# slave_node_v0_1.net
KiCad netlist of a schematic drawn in EAGLE
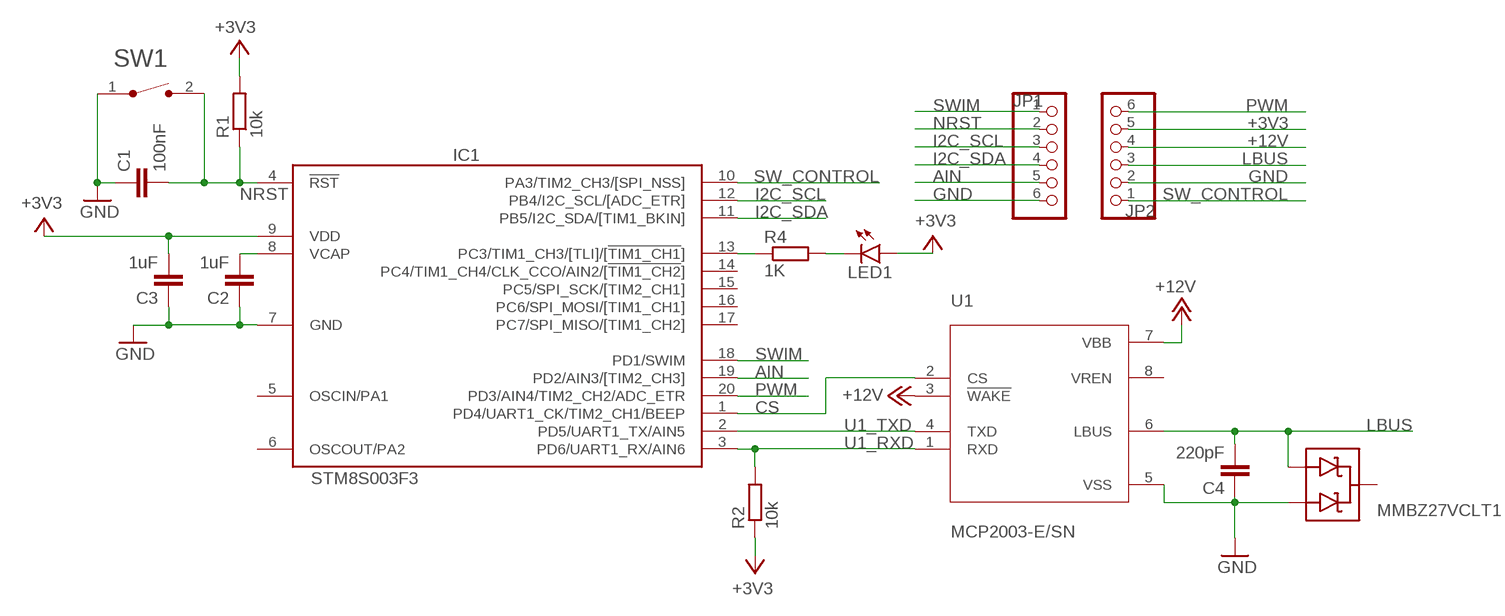
[diagram p0: schematic, sheet 1]
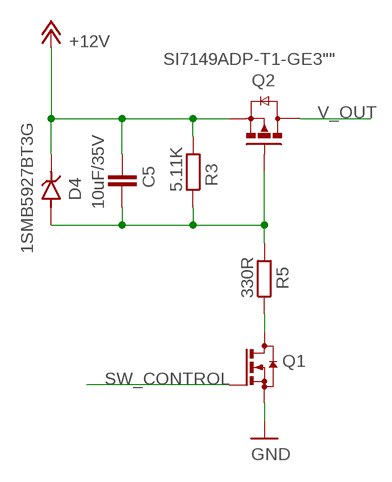
[diagram p1: schematic, sheet 2]
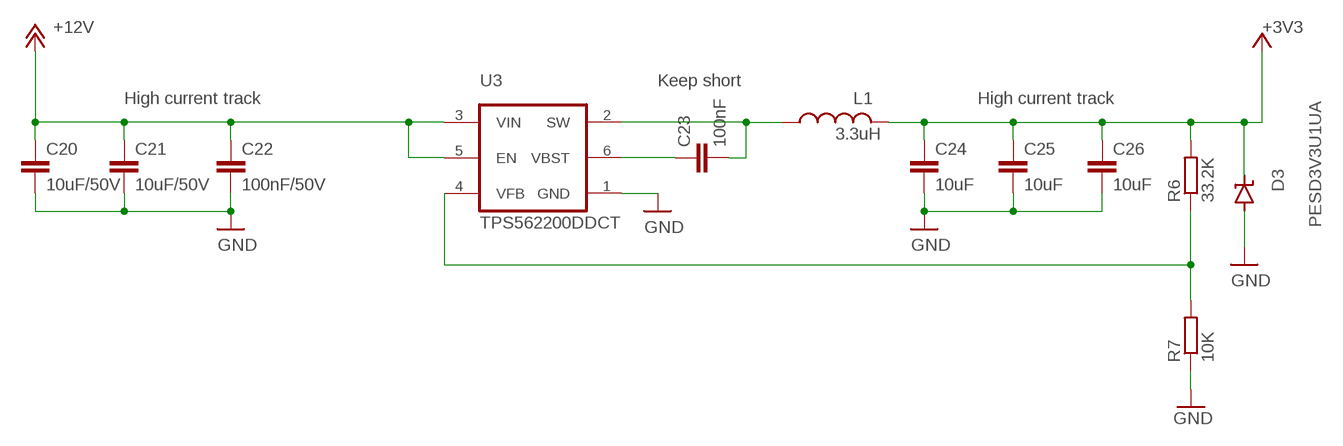
[diagram p2: schematic, sheet 3]

(export (version "E")
  (design (tool "Eeschema 10.0.6"))
  (components
    (comp (ref "C20")
      (value "10uF/50V")
      (footprint "eagle-import:C0603")
      (libsource (lib "eagle-import") (part "C-EUC0603"))
    )
    (comp (ref "C21")
      (value "10uF/50V")
      (footprint "eagle-import:C0603")
      (libsource (lib "eagle-import") (part "C-EUC0603"))
    )
    (comp (ref "C22")
      (value "100nF/50V")
      (footprint "eagle-import:C0603")
      (libsource (lib "eagle-import") (part "C-EUC0603"))
    )
    (comp (ref "C23")
      (value "100nF")
      (footprint "eagle-import:C0603")
      (libsource (lib "eagle-import") (part "C-EUC0603"))
    )
    (comp (ref "C24")
      (value "10uF")
      (footprint "eagle-import:C0603")
      (libsource (lib "eagle-import") (part "C-EUC0603"))
    )
    (comp (ref "C25")
      (value "10uF")
      (footprint "eagle-import:C0603")
      (libsource (lib "eagle-import") (part "C-EUC0603"))
    )
    (comp (ref "C26")
      (value "10uF")
      (footprint "eagle-import:C0603")
      (libsource (lib "eagle-import") (part "C-EUC0603"))
    )
    (comp (ref "D3")
      (value "PESD3V3U1UA")
      (footprint "eagle-import:SOD323")
      (libsource (lib "eagle-import") (part "PESD3V3U1UA"))
    )
    (comp (ref "L1")
      (value "3.3uH")
      (footprint "eagle-import:INDC2520X120N")
      (fields
        (field (name "DIGI-KEY_PART_NUMBER") "587-4723-1-ND")
        (field (name "MF") "Taiyo Yuden")
        (field (name "MP") "MBMK2520H3R3M")
      )
      (libsource (lib "eagle-import") (part "MBMK2520H3R3M"))
    )
    (comp (ref "R6")
      (value "33.2K")
      (footprint "eagle-import:R0603")
      (libsource (lib "eagle-import") (part "R-EU_R0603"))
    )
    (comp (ref "R7")
      (value "10K")
      (footprint "eagle-import:R0603")
      (libsource (lib "eagle-import") (part "R-EU_R0603"))
    )
    (comp (ref "U3")
      (value "TPS562200DDCT")
      (footprint "eagle-import:SOT95P280X110-6N")
      (fields (field (name "MF") "Texas Instruments"))
      (libsource (lib "eagle-import") (part "TPS562200DDCT"))
    )
    (comp (ref "C1")
      (value "100nF")
      (footprint "eagle-import:C0603")
      (libsource (lib "eagle-import") (part "C-EUC0603"))
    )
    (comp (ref "C2")
      (value "1uF")
      (footprint "eagle-import:C0603")
      (libsource (lib "eagle-import") (part "C-EUC0603"))
    )
    (comp (ref "C3")
      (value "1uF")
      (footprint "eagle-import:C0603")
      (libsource (lib "eagle-import") (part "C-EUC0603"))
    )
    (comp (ref "C4")
      (value "220pF")
      (footprint "eagle-import:C0603")
      (libsource (lib "eagle-import") (part "C-EUC0603"))
    )
    (comp (ref "D2")
      (value "MMBZ27VCLT1")
      (footprint "eagle-import:SOT23-3")
      (fields (field (name "MF") "ON Semiconductor") (field (name "SPICEPREFIX") "U"))
      (libsource (lib "eagle-import") (part "MMBZ27VCLT1"))
    )
    (comp (ref "IC1")
      (value "STM8S003F3")
      (footprint "eagle-import:TSSOP20")
      (libsource (lib "eagle-import") (part "STM8S003F3"))
    )
    (comp (ref "JP1")
      (value "PINHD-1X6")
      (footprint "eagle-import:1X06")
      (libsource (lib "eagle-import") (part "PINHD-1X6"))
    )
    (comp (ref "JP2")
      (value "PINHD-1X6")
      (footprint "eagle-import:1X06")
      (libsource (lib "eagle-import") (part "PINHD-1X6"))
    )
    (comp (ref "LED1")
      (value "LEDCHIP-LED0603")
      (footprint "eagle-import:CHIP-LED0603")
      (libsource (lib "eagle-import") (part "LEDCHIP-LED0603"))
    )
    (comp (ref "R1")
      (value "10k")
      (footprint "eagle-import:R0603")
      (libsource (lib "eagle-import") (part "R-EU_R0603"))
    )
    (comp (ref "R2")
      (value "10k")
      (footprint "eagle-import:R0603")
      (libsource (lib "eagle-import") (part "R-EU_R0603"))
    )
    (comp (ref "R4")
      (value "1K")
      (footprint "eagle-import:R0603")
      (libsource (lib "eagle-import") (part "R-EU_R0603"))
    )
    (comp (ref "SW1")
      (value "FSMSM")
      (footprint "eagle-import:TE_FSMSM")
      (fields (field (name "COMMENT") "1437566-3") (field (name "MF") "TE Connectivity"))
      (libsource (lib "eagle-import") (part "FSMSM"))
    )
    (comp (ref "U1")
      (value "MCP2003-E/SN")
      (footprint "eagle-import:SOIC127P600X175-8N")
      (fields (field (name "MF") "Microchip"))
      (libsource (lib "eagle-import") (part "MCP2003-E/SN"))
    )
    (comp (ref "C5")
      (value "C-EUC0603")
      (footprint "eagle-import:C0603")
      (fields (field (name "C1") "10uF/35V"))
      (libsource (lib "eagle-import") (part "C-EUC0603"))
    )
    (comp (ref "D4")
      (value "1SMB5927BT3G")
      (footprint "eagle-import:DIOM5436X247N")
      (fields (field (name "MF") "ON Semiconductor"))
      (libsource (lib "eagle-import") (part "1SMB5927BT3G"))
    )
    (comp (ref "Q1")
      (value "BSS123")
      (footprint "eagle-import:SOT23")
      (libsource (lib "eagle-import") (part "BSS123"))
    )
    (comp (ref "Q2")
      (value "SI7149ADP-T1-GE3\"\"")
      (footprint "eagle-import:POWERPAKSO-8")
      (libsource (lib "eagle-import") (part "SI7149ADP-T1-GE3{dblquote}{dblquote}"))
    )
    (comp (ref "R3")
      (value "R-EU_R0603")
      (footprint "eagle-import:R0603")
      (fields (field (name "R2") "5.11K"))
      (libsource (lib "eagle-import") (part "R-EU_R0603"))
    )
    (comp (ref "R5")
      (value "R-EU_R0603")
      (footprint "eagle-import:R0603")
      (fields (field (name "R3") "330R"))
      (libsource (lib "eagle-import") (part "R-EU_R0603"))
    )
  )
  (nets
    (net (code "1") (name "+3V3") (class "Default")
      (node (ref "C24") (pin "1") (pinfunction "1_1") (pintype "passive"))
      (node (ref "C25") (pin "1") (pinfunction "1_1") (pintype "passive"))
      (node (ref "C26") (pin "1") (pinfunction "1_1") (pintype "passive"))
      (node (ref "C3") (pin "2") (pinfunction "2_2") (pintype "passive"))
      (node (ref "D3") (pin "C") (pinfunction "C_C") (pintype "passive"))
      (node (ref "IC1") (pin "9") (pinfunction "VDD_9") (pintype "power_in"))
      (node (ref "JP2") (pin "5") (pinfunction "5_5") (pintype "passive"))
      (node (ref "L1") (pin "2") (pinfunction "2_2") (pintype "passive"))
      (node (ref "LED1") (pin "A") (pinfunction "A_A") (pintype "passive"))
      (node (ref "R1") (pin "2") (pinfunction "2_2") (pintype "passive"))
      (node (ref "R2") (pin "1") (pinfunction "1_1") (pintype "passive"))
      (node (ref "R6") (pin "2") (pinfunction "2_2") (pintype "passive"))
    )
    (net (code "2") (name "+12V") (class "Default")
      (node (ref "C20") (pin "1") (pinfunction "1_1") (pintype "passive"))
      (node (ref "C21") (pin "1") (pinfunction "1_1") (pintype "passive"))
      (node (ref "C22") (pin "1") (pinfunction "1_1") (pintype "passive"))
      (node (ref "C5") (pin "1") (pinfunction "1_1") (pintype "passive"))
      (node (ref "D4") (pin "C") (pinfunction "K_C") (pintype "passive"))
      (node (ref "JP2") (pin "4") (pinfunction "4_4") (pintype "passive"))
      (node (ref "Q2") (pin "1") (pinfunction "S_1") (pintype "passive"))
      (node (ref "Q2") (pin "2") (pinfunction "S_2") (pintype "passive"))
      (node (ref "Q2") (pin "3") (pinfunction "S_3") (pintype "passive"))
      (node (ref "R3") (pin "2") (pinfunction "2_2") (pintype "passive"))
      (node (ref "U1") (pin "3") (pinfunction "~{WAKE}_3") (pintype "input"))
      (node (ref "U1") (pin "7") (pinfunction "VBB_7") (pintype "power_in"))
      (node (ref "U3") (pin "3") (pinfunction "VIN_3") (pintype "input"))
      (node (ref "U3") (pin "5") (pinfunction "EN_5") (pintype "input"))
    )
    (net (code "3") (name "AIN") (class "Default")
      (node (ref "IC1") (pin "19") (pinfunction "PD2/AIN3/[TIM2_CH3]_19") (pintype "bidirectional"))
      (node (ref "JP1") (pin "5") (pinfunction "5_5") (pintype "passive"))
    )
    (net (code "4") (name "CS") (class "Default")
      (node (ref "IC1") (pin "1") (pinfunction "PD4/UART1_CK/TIM2_CH1/BEEP_1") (pintype "bidirectional"))
      (node (ref "U1") (pin "2") (pinfunction "CS_2") (pintype "input"))
    )
    (net (code "5") (name "GND") (class "Default")
      (node (ref "C1") (pin "1") (pinfunction "1_1") (pintype "passive"))
      (node (ref "C2") (pin "1") (pinfunction "1_1") (pintype "passive"))
      (node (ref "C20") (pin "2") (pinfunction "2_2") (pintype "passive"))
      (node (ref "C21") (pin "2") (pinfunction "2_2") (pintype "passive"))
      (node (ref "C22") (pin "2") (pinfunction "2_2") (pintype "passive"))
      (node (ref "C24") (pin "2") (pinfunction "2_2") (pintype "passive"))
      (node (ref "C25") (pin "2") (pinfunction "2_2") (pintype "passive"))
      (node (ref "C26") (pin "2") (pinfunction "2_2") (pintype "passive"))
      (node (ref "C3") (pin "1") (pinfunction "1_1") (pintype "passive"))
      (node (ref "C4") (pin "1") (pinfunction "1_1") (pintype "passive"))
      (node (ref "D2") (pin "1") (pinfunction "A1_1") (pintype "passive"))
      (node (ref "D3") (pin "A") (pinfunction "A_A") (pintype "passive"))
      (node (ref "IC1") (pin "7") (pinfunction "GND_7") (pintype "power_in"))
      (node (ref "JP1") (pin "6") (pinfunction "6_6") (pintype "passive"))
      (node (ref "JP2") (pin "2") (pinfunction "2_2") (pintype "passive"))
      (node (ref "Q1") (pin "2") (pinfunction "S_2") (pintype "passive"))
      (node (ref "R7") (pin "1") (pinfunction "1_1") (pintype "passive"))
      (node (ref "SW1") (pin "1") (pinfunction "1_1") (pintype "passive"))
      (node (ref "U1") (pin "5") (pinfunction "VSS_5") (pintype "power_in"))
      (node (ref "U3") (pin "1") (pinfunction "GND_1") (pintype "power_in"))
    )
    (net (code "6") (name "I2C_SCL") (class "Default")
      (node (ref "IC1") (pin "12") (pinfunction "PB4/I2C_SCL/[ADC_ETR]_12") (pintype "bidirectional"))
      (node (ref "JP1") (pin "3") (pinfunction "3_3") (pintype "passive"))
    )
    (net (code "7") (name "I2C_SDA") (class "Default")
      (node (ref "IC1") (pin "11") (pinfunction "PB5/I2C_SDA/[TIM1_BKIN]_11") (pintype "bidirectional"))
      (node (ref "JP1") (pin "4") (pinfunction "4_4") (pintype "passive"))
    )
    (net (code "8") (name "LBUS") (class "Default")
      (node (ref "C4") (pin "2") (pinfunction "2_2") (pintype "passive"))
      (node (ref "D2") (pin "2") (pinfunction "A2_2") (pintype "passive"))
      (node (ref "JP2") (pin "3") (pinfunction "3_3") (pintype "passive"))
      (node (ref "U1") (pin "6") (pinfunction "LBUS_6") (pintype "bidirectional"))
    )
    (net (code "9") (name "NRST") (class "Default")
      (node (ref "C1") (pin "2") (pinfunction "2_2") (pintype "passive"))
      (node (ref "IC1") (pin "4") (pinfunction "~{RST}_4") (pintype "input"))
      (node (ref "JP1") (pin "2") (pinfunction "2_2") (pintype "passive"))
      (node (ref "R1") (pin "1") (pinfunction "1_1") (pintype "passive"))
      (node (ref "SW1") (pin "2") (pinfunction "2_2") (pintype "passive"))
    )
    (net (code "10") (name "Net-(IC1-PC3{slash}TIM1_CH3{slash}[TLI]{slash}[~{TIM1_CH1}])") (class "Default")
      (node (ref "IC1") (pin "13") (pinfunction "PC3/TIM1_CH3/[TLI]/[~{TIM1_CH1}]_13") (pintype "bidirectional"))
      (node (ref "R4") (pin "1") (pinfunction "1_1") (pintype "passive"))
    )
    (net (code "11") (name "Net-(IC1-VCAP)") (class "Default")
      (node (ref "C2") (pin "2") (pinfunction "2_2") (pintype "passive"))
      (node (ref "IC1") (pin "8") (pinfunction "VCAP_8") (pintype "power_in"))
    )
    (net (code "12") (name "Net-(LED1-PadC)") (class "Default")
      (node (ref "LED1") (pin "C") (pinfunction "C_C") (pintype "passive"))
      (node (ref "R4") (pin "2") (pinfunction "2_2") (pintype "passive"))
    )
    (net (code "13") (name "Net-(Q1-D)") (class "Default")
      (node (ref "Q1") (pin "3") (pinfunction "D_3") (pintype "passive"))
      (node (ref "R5") (pin "1") (pinfunction "1_1") (pintype "passive"))
    )
    (net (code "14") (name "Net-(Q2-G)") (class "Default")
      (node (ref "C5") (pin "2") (pinfunction "2_2") (pintype "passive"))
      (node (ref "D4") (pin "A") (pinfunction "A_A") (pintype "passive"))
      (node (ref "Q2") (pin "4") (pinfunction "G_4") (pintype "passive"))
      (node (ref "R3") (pin "1") (pinfunction "1_1") (pintype "passive"))
      (node (ref "R5") (pin "2") (pinfunction "2_2") (pintype "passive"))
    )
    (net (code "15") (name "Net-(U3-SW)") (class "Default")
      (node (ref "C23") (pin "2") (pinfunction "2_2") (pintype "passive"))
      (node (ref "L1") (pin "1") (pinfunction "1_1") (pintype "passive"))
      (node (ref "U3") (pin "2") (pinfunction "SW_2") (pintype "output"))
    )
    (net (code "16") (name "Net-(U3-VBST)") (class "Default")
      (node (ref "C23") (pin "1") (pinfunction "1_1") (pintype "passive"))
      (node (ref "U3") (pin "6") (pinfunction "VBST_6") (pintype "power_in"))
    )
    (net (code "17") (name "Net-(U3-VFB)") (class "Default")
      (node (ref "R6") (pin "1") (pinfunction "1_1") (pintype "passive"))
      (node (ref "R7") (pin "2") (pinfunction "2_2") (pintype "passive"))
      (node (ref "U3") (pin "4") (pinfunction "VFB_4") (pintype "input"))
    )
    (net (code "18") (name "PWM") (class "Default")
      (node (ref "IC1") (pin "20") (pinfunction "PD3/AIN4/TIM2_CH2/ADC_ETR_20") (pintype "bidirectional"))
      (node (ref "JP2") (pin "6") (pinfunction "6_6") (pintype "passive"))
    )
    (net (code "19") (name "SWIM") (class "Default")
      (node (ref "IC1") (pin "18") (pinfunction "PD1/SWIM_18") (pintype "bidirectional"))
      (node (ref "JP1") (pin "1") (pinfunction "1_1") (pintype "passive"))
    )
    (net (code "20") (name "SW_CONTROL") (class "Default")
      (node (ref "IC1") (pin "10") (pinfunction "PA3/TIM2_CH3/[SPI_NSS]_10") (pintype "bidirectional"))
      (node (ref "JP2") (pin "1") (pinfunction "1_1") (pintype "passive"))
      (node (ref "Q1") (pin "1") (pinfunction "G_1") (pintype "passive"))
    )
    (net (code "21") (name "U1_RXD") (class "Default")
      (node (ref "IC1") (pin "3") (pinfunction "PD6/UART1_RX/AIN6_3") (pintype "bidirectional"))
      (node (ref "R2") (pin "2") (pinfunction "2_2") (pintype "passive"))
      (node (ref "U1") (pin "1") (pinfunction "RXD_1") (pintype "output"))
    )
    (net (code "22") (name "U1_TXD") (class "Default")
      (node (ref "IC1") (pin "2") (pinfunction "PD5/UART1_TX/AIN5_2") (pintype "bidirectional"))
      (node (ref "U1") (pin "4") (pinfunction "TXD_4") (pintype "input"))
    )
    (net (code "23") (name "V_OUT") (class "Default")
      (node (ref "Q2") (pin "5") (pinfunction "D_5") (pintype "passive"))
      (node (ref "Q2") (pin "6") (pinfunction "D_6") (pintype "passive"))
      (node (ref "Q2") (pin "7") (pinfunction "D_7") (pintype "passive"))
      (node (ref "Q2") (pin "8") (pinfunction "D_8") (pintype "passive"))
      (node (ref "Q2") (pin "9") (pinfunction "D_9") (pintype "passive"))
    )
    (net (code "24") (name "unconnected-(D2-C-Pad3)") (class "Default")
      (node (ref "D2") (pin "3") (pinfunction "C_3") (pintype "passive"))
    )
    (net (code "25") (name "unconnected-(IC1-OSCIN{slash}PA1-Pad5)") (class "Default")
      (node (ref "IC1") (pin "5") (pinfunction "OSCIN/PA1_5") (pintype "bidirectional"))
    )
    (net (code "26") (name "unconnected-(IC1-OSCOUT{slash}PA2-Pad6)") (class "Default")
      (node (ref "IC1") (pin "6") (pinfunction "OSCOUT/PA2_6") (pintype "bidirectional"))
    )
    (net (code "27") (name "unconnected-(IC1-PC4{slash}TIM1_CH4{slash}CLK_CCO{slash}AIN2{slash}[~{TIM1_CH2}]-Pad14)") (class "Default")
      (node (ref "IC1") (pin "14") (pinfunction "PC4/TIM1_CH4/CLK_CCO/AIN2/[~{TIM1_CH2}]_14") (pintype "bidirectional"))
    )
    (net (code "28") (name "unconnected-(IC1-PC5{slash}SPI_SCK{slash}[TIM2_CH1]-Pad15)") (class "Default")
      (node (ref "IC1") (pin "15") (pinfunction "PC5/SPI_SCK/[TIM2_CH1]_15") (pintype "bidirectional"))
    )
    (net (code "29") (name "unconnected-(IC1-PC6{slash}SPI_MOSI{slash}[TIM1_CH1]-Pad16)") (class "Default")
      (node (ref "IC1") (pin "16") (pinfunction "PC6/SPI_MOSI/[TIM1_CH1]_16") (pintype "bidirectional"))
    )
    (net (code "30") (name "unconnected-(IC1-PC7{slash}SPI_MISO{slash}[TIM1_CH2]-Pad17)") (class "Default")
      (node (ref "IC1") (pin "17") (pinfunction "PC7/SPI_MISO/[TIM1_CH2]_17") (pintype "bidirectional"))
    )
    (net (code "31") (name "unconnected-(U1-VREN-Pad8)") (class "Default")
      (node (ref "U1") (pin "8") (pinfunction "VREN_8") (pintype "output"))
    )
  )
)
